# nRF52832_qfaa_nfc.net
KiCad netlist of a schematic drawn in EAGLE
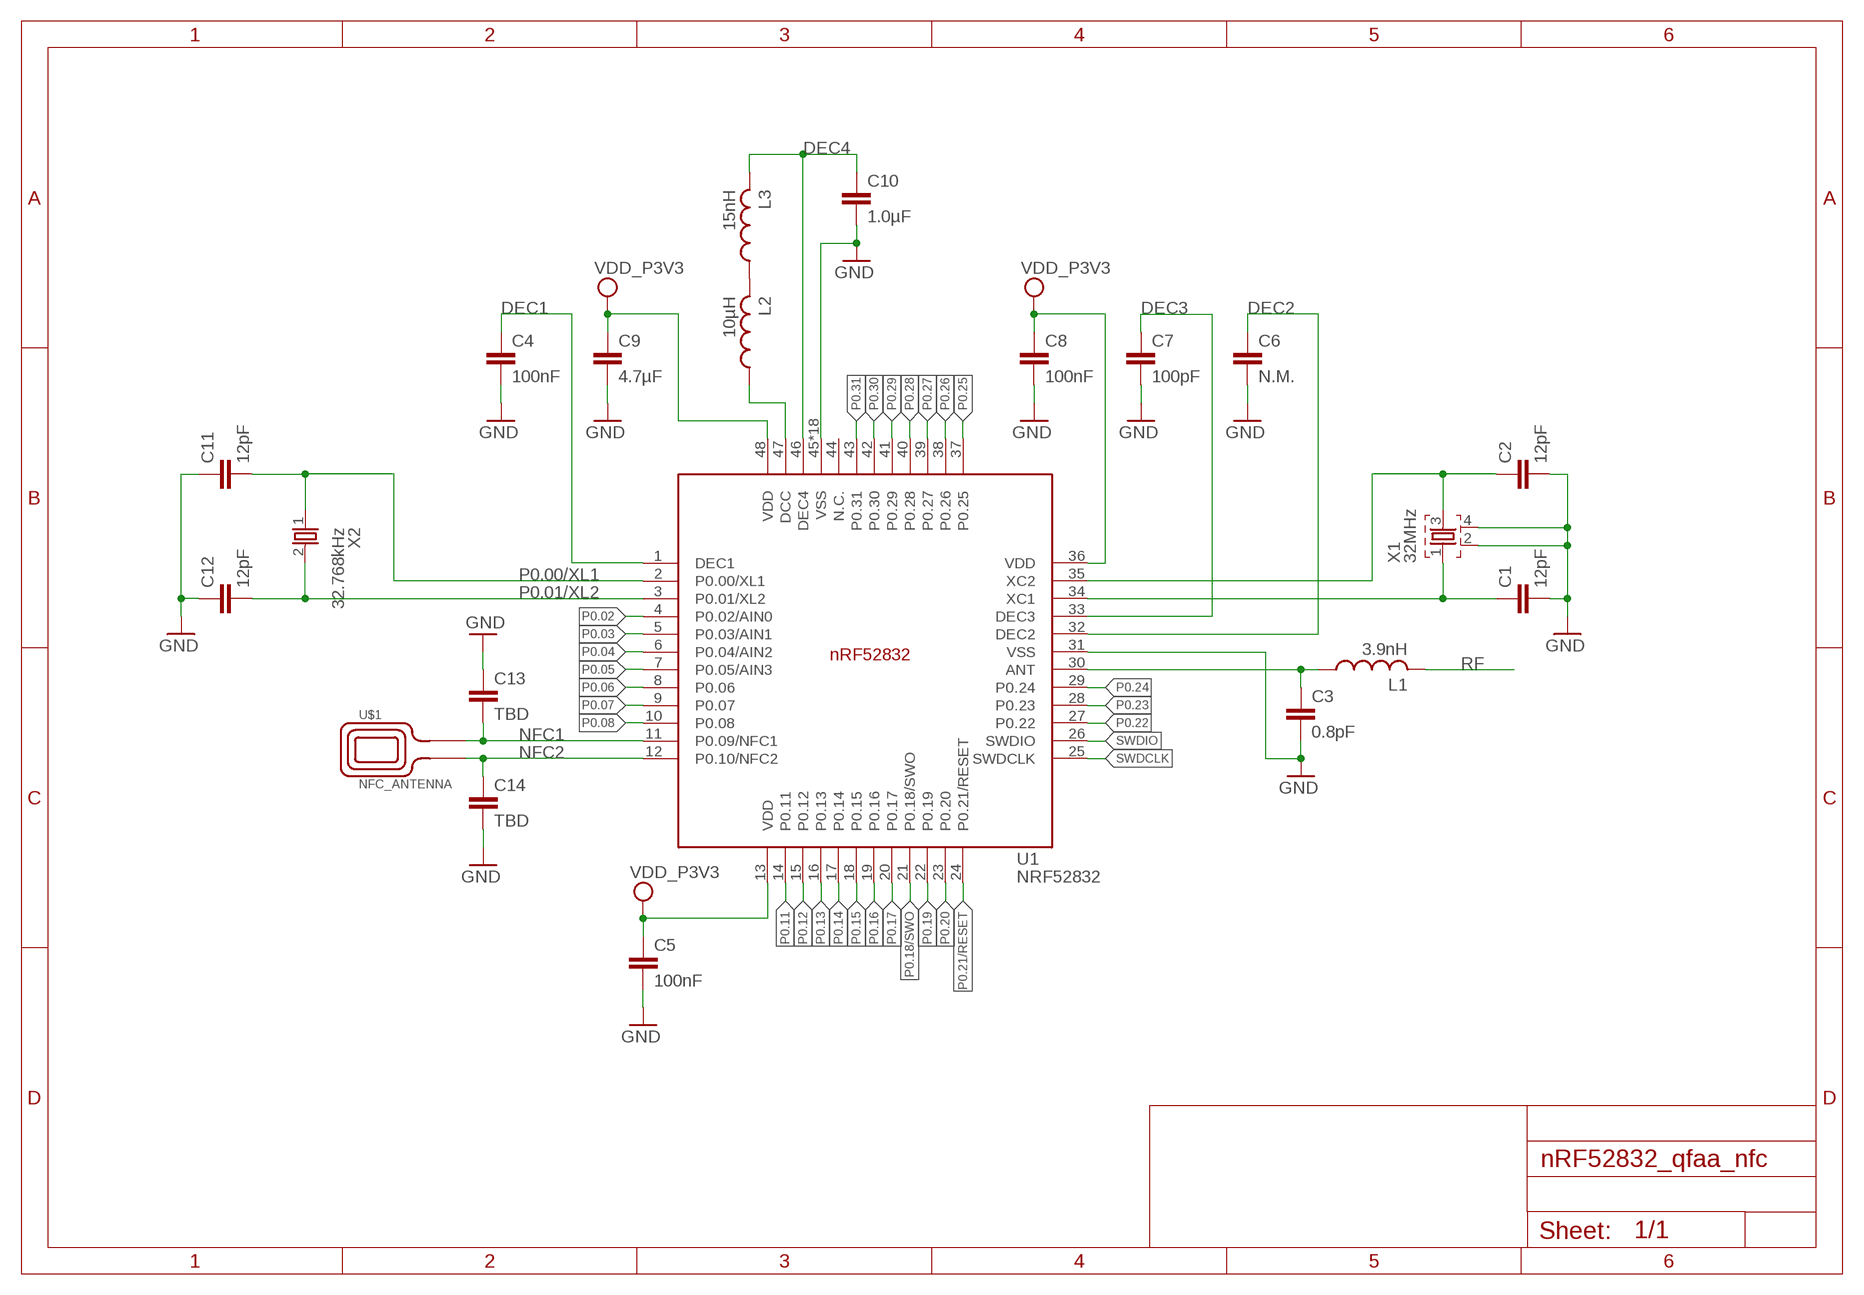
[diagram p0: schematic, sheet 1]

(export (version "E")
  (design (tool "Eeschema 10.0.6"))
  (components
    (comp (ref "C1")
      (value "12pF")
      (footprint "eagle-import:RESC0402_N")
      (libsource (lib "eagle-import") (part "CAPACITOR_0402_N"))
    )
    (comp (ref "C2")
      (value "12pF")
      (footprint "eagle-import:RESC0402_N")
      (libsource (lib "eagle-import") (part "CAPACITOR_0402_N"))
    )
    (comp (ref "C3")
      (value "0.8pF")
      (footprint "eagle-import:RESC0402_N")
      (libsource (lib "eagle-import") (part "CAPACITOR_0402_N"))
    )
    (comp (ref "C4")
      (value "100nF")
      (footprint "eagle-import:RESC0402_N")
      (libsource (lib "eagle-import") (part "CAPACITOR_0402_N"))
    )
    (comp (ref "C5")
      (value "100nF")
      (footprint "eagle-import:RESC0402_N")
      (libsource (lib "eagle-import") (part "CAPACITOR_0402_N"))
    )
    (comp (ref "C6")
      (value "N.M.")
      (footprint "eagle-import:RESC0402_N")
      (libsource (lib "eagle-import") (part "CAPACITOR_0402_N"))
    )
    (comp (ref "C7")
      (value "100pF")
      (footprint "eagle-import:RESC0402_N")
      (libsource (lib "eagle-import") (part "CAPACITOR_0402_N"))
    )
    (comp (ref "C8")
      (value "100nF")
      (footprint "eagle-import:RESC0402_N")
      (libsource (lib "eagle-import") (part "CAPACITOR_0402_N"))
    )
    (comp (ref "C9")
      (value "4.7µF")
      (footprint "eagle-import:RESC0603_N")
      (libsource (lib "eagle-import") (part "CAPACITOR_0603_N"))
    )
    (comp (ref "C10")
      (value "1.0µF")
      (footprint "eagle-import:RESC0603_N")
      (libsource (lib "eagle-import") (part "CAPACITOR_0603_N"))
    )
    (comp (ref "C11")
      (value "12pF")
      (footprint "eagle-import:RESC0402_N")
      (libsource (lib "eagle-import") (part "CAPACITOR_0402_N"))
    )
    (comp (ref "C12")
      (value "12pF")
      (footprint "eagle-import:RESC0402_N")
      (libsource (lib "eagle-import") (part "CAPACITOR_0402_N"))
    )
    (comp (ref "C13")
      (value "TBD")
      (footprint "eagle-import:RESC0402_N")
      (libsource (lib "eagle-import") (part "CAPACITOR_0402_N"))
    )
    (comp (ref "C14")
      (value "TBD")
      (footprint "eagle-import:RESC0402_N")
      (libsource (lib "eagle-import") (part "CAPACITOR_0402_N"))
    )
    (comp (ref "L1")
      (value "3.9nH")
      (footprint "eagle-import:RESC0402_N")
      (libsource (lib "eagle-import") (part "INDUCTOR_0402_N"))
    )
    (comp (ref "L2")
      (value "10µH")
      (footprint "eagle-import:RESC0603_N")
      (libsource (lib "eagle-import") (part "INDUCTOR_0603_N"))
    )
    (comp (ref "L3")
      (value "15nH")
      (footprint "eagle-import:RESC0402_N")
      (libsource (lib "eagle-import") (part "INDUCTOR_0402_N"))
    )
    (comp (ref "U$1")
      (value "NFC_ANTENNA")
      (footprint "eagle-import:NFC_ANT")
      (libsource (lib "eagle-import") (part "NFC_ANTENNA"))
    )
    (comp (ref "U1")
      (value "NRF52832")
      (footprint "eagle-import:QFN40P600X600X90-48_N")
      (libsource (lib "eagle-import") (part "NRF52832"))
    )
    (comp (ref "X1")
      (value "32MHz")
      (footprint "eagle-import:BT-XTAL_2016_N")
      (libsource (lib "eagle-import") (part "XTAL_32MHZ"))
    )
    (comp (ref "X2")
      (value "32.768kHz")
      (footprint "eagle-import:XTAL_3215_N")
      (libsource (lib "eagle-import") (part "XTAL_32KHZ"))
    )
  )
  (nets
    (net (code "1") (name "/DEC1") (class "Default")
      (node (ref "C4") (pin "1") (pinfunction "1_1") (pintype "passive"))
      (node (ref "U1") (pin "1") (pinfunction "DEC1_1") (pintype "power_in"))
    )
    (net (code "2") (name "/DEC2") (class "Default")
      (node (ref "C6") (pin "1") (pinfunction "1_1") (pintype "passive"))
      (node (ref "U1") (pin "32") (pinfunction "DEC2_32") (pintype "bidirectional"))
    )
    (net (code "3") (name "/DEC3") (class "Default")
      (node (ref "C7") (pin "1") (pinfunction "1_1") (pintype "passive"))
      (node (ref "U1") (pin "33") (pinfunction "DEC3_33") (pintype "bidirectional"))
    )
    (net (code "4") (name "/DEC4") (class "Default")
      (node (ref "C10") (pin "1") (pinfunction "1_1") (pintype "passive"))
      (node (ref "L3") (pin "2") (pinfunction "2_2") (pintype "passive"))
      (node (ref "U1") (pin "46") (pinfunction "DEC4_46") (pintype "power_in"))
    )
    (net (code "5") (name "/NFC1") (class "Default")
      (node (ref "C13") (pin "2") (pinfunction "2_2") (pintype "passive"))
      (node (ref "U$1") (pin "2") (pinfunction "P$2_2") (pintype "bidirectional"))
      (node (ref "U1") (pin "11") (pinfunction "P0.09/NFC1_11") (pintype "bidirectional"))
    )
    (net (code "6") (name "/NFC2") (class "Default")
      (node (ref "C14") (pin "1") (pinfunction "1_1") (pintype "passive"))
      (node (ref "U$1") (pin "1") (pinfunction "P$1_1") (pintype "bidirectional"))
      (node (ref "U1") (pin "12") (pinfunction "P0.10/NFC2_12") (pintype "bidirectional"))
    )
    (net (code "7") (name "/P0.00{slash}XL1") (class "Default")
      (node (ref "C11") (pin "2") (pinfunction "2_2") (pintype "passive"))
      (node (ref "U1") (pin "2") (pinfunction "P0.00/XL1_2") (pintype "bidirectional"))
      (node (ref "X2") (pin "1") (pinfunction "1_1") (pintype "passive"))
    )
    (net (code "8") (name "/P0.01{slash}XL2") (class "Default")
      (node (ref "C12") (pin "2") (pinfunction "2_2") (pintype "passive"))
      (node (ref "U1") (pin "3") (pinfunction "P0.01/XL2_3") (pintype "bidirectional"))
      (node (ref "X2") (pin "2") (pinfunction "2_2") (pintype "passive"))
    )
    (net (code "9") (name "/RF") (class "Default")
      (node (ref "L1") (pin "2") (pinfunction "2_2") (pintype "passive"))
    )
    (net (code "10") (name "GND") (class "Default")
      (node (ref "C1") (pin "2") (pinfunction "2_2") (pintype "passive"))
      (node (ref "C10") (pin "2") (pinfunction "2_2") (pintype "passive"))
      (node (ref "C11") (pin "1") (pinfunction "1_1") (pintype "passive"))
      (node (ref "C12") (pin "1") (pinfunction "1_1") (pintype "passive"))
      (node (ref "C13") (pin "1") (pinfunction "1_1") (pintype "passive"))
      (node (ref "C14") (pin "2") (pinfunction "2_2") (pintype "passive"))
      (node (ref "C2") (pin "2") (pinfunction "2_2") (pintype "passive"))
      (node (ref "C3") (pin "2") (pinfunction "2_2") (pintype "passive"))
      (node (ref "C4") (pin "2") (pinfunction "2_2") (pintype "passive"))
      (node (ref "C5") (pin "2") (pinfunction "2_2") (pintype "passive"))
      (node (ref "C6") (pin "2") (pinfunction "2_2") (pintype "passive"))
      (node (ref "C7") (pin "2") (pinfunction "2_2") (pintype "passive"))
      (node (ref "C8") (pin "2") (pinfunction "2_2") (pintype "passive"))
      (node (ref "C9") (pin "2") (pinfunction "2_2") (pintype "passive"))
      (node (ref "U1") (pin "31") (pinfunction "VSS_31") (pintype "bidirectional"))
      (node (ref "U1") (pin "45") (pinfunction "VSS_45") (pintype "power_in"))
      (node (ref "U1") (pin "PAD") (pinfunction "VSS_PAD") (pintype "power_in"))
      (node (ref "U1") (pin "PAD@VIA01") (pinfunction "VSS_PAD@VIA01") (pintype "power_in"))
      (node (ref "U1") (pin "PAD@VIA02") (pinfunction "VSS_PAD@VIA02") (pintype "power_in"))
      (node (ref "U1") (pin "PAD@VIA03") (pinfunction "VSS_PAD@VIA03") (pintype "power_in"))
      (node (ref "U1") (pin "PAD@VIA04") (pinfunction "VSS_PAD@VIA04") (pintype "power_in"))
      (node (ref "U1") (pin "PAD@VIA05") (pinfunction "VSS_PAD@VIA05") (pintype "power_in"))
      (node (ref "U1") (pin "PAD@VIA06") (pinfunction "VSS_PAD@VIA06") (pintype "power_in"))
      (node (ref "U1") (pin "PAD@VIA07") (pinfunction "VSS_PAD@VIA07") (pintype "power_in"))
      (node (ref "U1") (pin "PAD@VIA08") (pinfunction "VSS_PAD@VIA08") (pintype "power_in"))
      (node (ref "U1") (pin "PAD@VIA09") (pinfunction "VSS_PAD@VIA09") (pintype "power_in"))
      (node (ref "U1") (pin "PAD@VIA10") (pinfunction "VSS_PAD@VIA10") (pintype "power_in"))
      (node (ref "U1") (pin "PAD@VIA11") (pinfunction "VSS_PAD@VIA11") (pintype "power_in"))
      (node (ref "U1") (pin "PAD@VIA12") (pinfunction "VSS_PAD@VIA12") (pintype "power_in"))
      (node (ref "U1") (pin "PAD@VIA13") (pinfunction "VSS_PAD@VIA13") (pintype "power_in"))
      (node (ref "U1") (pin "PAD@VIA14") (pinfunction "VSS_PAD@VIA14") (pintype "power_in"))
      (node (ref "U1") (pin "PAD@VIA15") (pinfunction "VSS_PAD@VIA15") (pintype "power_in"))
      (node (ref "U1") (pin "PAD@VIA16") (pinfunction "VSS_PAD@VIA16") (pintype "power_in"))
      (node (ref "X1") (pin "2") (pinfunction "2_2") (pintype "passive"))
      (node (ref "X1") (pin "4") (pinfunction "4_4") (pintype "passive"))
    )
    (net (code "11") (name "Net-(L2-Pad2)") (class "Default")
      (node (ref "L2") (pin "2") (pinfunction "2_2") (pintype "passive"))
      (node (ref "L3") (pin "1") (pinfunction "1_1") (pintype "passive"))
    )
    (net (code "12") (name "Net-(U1-ANT)") (class "Default")
      (node (ref "C3") (pin "1") (pinfunction "1_1") (pintype "passive"))
      (node (ref "L1") (pin "1") (pinfunction "1_1") (pintype "passive"))
      (node (ref "U1") (pin "30") (pinfunction "ANT_30") (pintype "bidirectional"))
    )
    (net (code "13") (name "Net-(U1-DCC)") (class "Default")
      (node (ref "L2") (pin "1") (pinfunction "1_1") (pintype "passive"))
      (node (ref "U1") (pin "47") (pinfunction "DCC_47") (pintype "output"))
    )
    (net (code "14") (name "Net-(U1-XC1)") (class "Default")
      (node (ref "C1") (pin "1") (pinfunction "1_1") (pintype "passive"))
      (node (ref "U1") (pin "34") (pinfunction "XC1_34") (pintype "input"))
      (node (ref "X1") (pin "1") (pinfunction "1_1") (pintype "passive"))
    )
    (net (code "15") (name "Net-(U1-XC2)") (class "Default")
      (node (ref "C2") (pin "1") (pinfunction "1_1") (pintype "passive"))
      (node (ref "U1") (pin "35") (pinfunction "XC2_35") (pintype "output"))
      (node (ref "X1") (pin "3") (pinfunction "3_3") (pintype "passive"))
    )
    (net (code "16") (name "P0.02") (class "Default")
      (node (ref "U1") (pin "4") (pinfunction "P0.02/AIN0_4") (pintype "bidirectional"))
    )
    (net (code "17") (name "P0.03") (class "Default")
      (node (ref "U1") (pin "5") (pinfunction "P0.03/AIN1_5") (pintype "bidirectional"))
    )
    (net (code "18") (name "P0.04") (class "Default")
      (node (ref "U1") (pin "6") (pinfunction "P0.04/AIN2_6") (pintype "bidirectional"))
    )
    (net (code "19") (name "P0.05") (class "Default")
      (node (ref "U1") (pin "7") (pinfunction "P0.05/AIN3_7") (pintype "bidirectional"))
    )
    (net (code "20") (name "P0.06") (class "Default")
      (node (ref "U1") (pin "8") (pinfunction "P0.06_8") (pintype "bidirectional"))
    )
    (net (code "21") (name "P0.07") (class "Default")
      (node (ref "U1") (pin "9") (pinfunction "P0.07_9") (pintype "bidirectional"))
    )
    (net (code "22") (name "P0.08") (class "Default")
      (node (ref "U1") (pin "10") (pinfunction "P0.08_10") (pintype "bidirectional"))
    )
    (net (code "23") (name "P0.11") (class "Default")
      (node (ref "U1") (pin "14") (pinfunction "P0.11_14") (pintype "bidirectional"))
    )
    (net (code "24") (name "P0.12") (class "Default")
      (node (ref "U1") (pin "15") (pinfunction "P0.12_15") (pintype "bidirectional"))
    )
    (net (code "25") (name "P0.13") (class "Default")
      (node (ref "U1") (pin "16") (pinfunction "P0.13_16") (pintype "bidirectional"))
    )
    (net (code "26") (name "P0.14") (class "Default")
      (node (ref "U1") (pin "17") (pinfunction "P0.14_17") (pintype "bidirectional"))
    )
    (net (code "27") (name "P0.15") (class "Default")
      (node (ref "U1") (pin "18") (pinfunction "P0.15_18") (pintype "bidirectional"))
    )
    (net (code "28") (name "P0.16") (class "Default")
      (node (ref "U1") (pin "19") (pinfunction "P0.16_19") (pintype "bidirectional"))
    )
    (net (code "29") (name "P0.17") (class "Default")
      (node (ref "U1") (pin "20") (pinfunction "P0.17_20") (pintype "bidirectional"))
    )
    (net (code "30") (name "P0.18{slash}SWO") (class "Default")
      (node (ref "U1") (pin "21") (pinfunction "P0.18/SWO_21") (pintype "bidirectional"))
    )
    (net (code "31") (name "P0.19") (class "Default")
      (node (ref "U1") (pin "22") (pinfunction "P0.19_22") (pintype "bidirectional"))
    )
    (net (code "32") (name "P0.20") (class "Default")
      (node (ref "U1") (pin "23") (pinfunction "P0.20_23") (pintype "bidirectional"))
    )
    (net (code "33") (name "P0.21{slash}RESET") (class "Default")
      (node (ref "U1") (pin "24") (pinfunction "P0.21/RESET_24") (pintype "bidirectional"))
    )
    (net (code "34") (name "P0.22") (class "Default")
      (node (ref "U1") (pin "27") (pinfunction "P0.22_27") (pintype "bidirectional"))
    )
    (net (code "35") (name "P0.23") (class "Default")
      (node (ref "U1") (pin "28") (pinfunction "P0.23_28") (pintype "bidirectional"))
    )
    (net (code "36") (name "P0.24") (class "Default")
      (node (ref "U1") (pin "29") (pinfunction "P0.24_29") (pintype "bidirectional"))
    )
    (net (code "37") (name "P0.25") (class "Default")
      (node (ref "U1") (pin "37") (pinfunction "P0.25_37") (pintype "bidirectional"))
    )
    (net (code "38") (name "P0.26") (class "Default")
      (node (ref "U1") (pin "38") (pinfunction "P0.26_38") (pintype "bidirectional"))
    )
    (net (code "39") (name "P0.27") (class "Default")
      (node (ref "U1") (pin "39") (pinfunction "P0.27_39") (pintype "bidirectional"))
    )
    (net (code "40") (name "P0.28") (class "Default")
      (node (ref "U1") (pin "40") (pinfunction "P0.28_40") (pintype "bidirectional"))
    )
    (net (code "41") (name "P0.29") (class "Default")
      (node (ref "U1") (pin "41") (pinfunction "P0.29_41") (pintype "bidirectional"))
    )
    (net (code "42") (name "P0.30") (class "Default")
      (node (ref "U1") (pin "42") (pinfunction "P0.30_42") (pintype "bidirectional"))
    )
    (net (code "43") (name "P0.31") (class "Default")
      (node (ref "U1") (pin "43") (pinfunction "P0.31_43") (pintype "bidirectional"))
    )
    (net (code "44") (name "SWDCLK") (class "Default")
      (node (ref "U1") (pin "25") (pinfunction "SWDCLK_25") (pintype "input"))
    )
    (net (code "45") (name "SWDIO") (class "Default")
      (node (ref "U1") (pin "26") (pinfunction "SWDIO_26") (pintype "bidirectional"))
    )
    (net (code "46") (name "VDD_P3V3") (class "Default")
      (node (ref "C5") (pin "1") (pinfunction "1_1") (pintype "passive"))
      (node (ref "C8") (pin "1") (pinfunction "1_1") (pintype "passive"))
      (node (ref "C9") (pin "1") (pinfunction "1_1") (pintype "passive"))
      (node (ref "U1") (pin "13") (pinfunction "VDD_13") (pintype "power_in"))
      (node (ref "U1") (pin "36") (pinfunction "VDD_36") (pintype "power_in"))
      (node (ref "U1") (pin "48") (pinfunction "VDD_48") (pintype "power_in"))
    )
    (net (code "47") (name "unconnected-(U1-N.C.-Pad44)") (class "Default")
      (node (ref "U1") (pin "44") (pinfunction "N.C._44") (pintype "no_connect"))
    )
  )
)
